# Power_Supply_No_Slo_Start.net
KiCad netlist of a schematic drawn in EAGLE
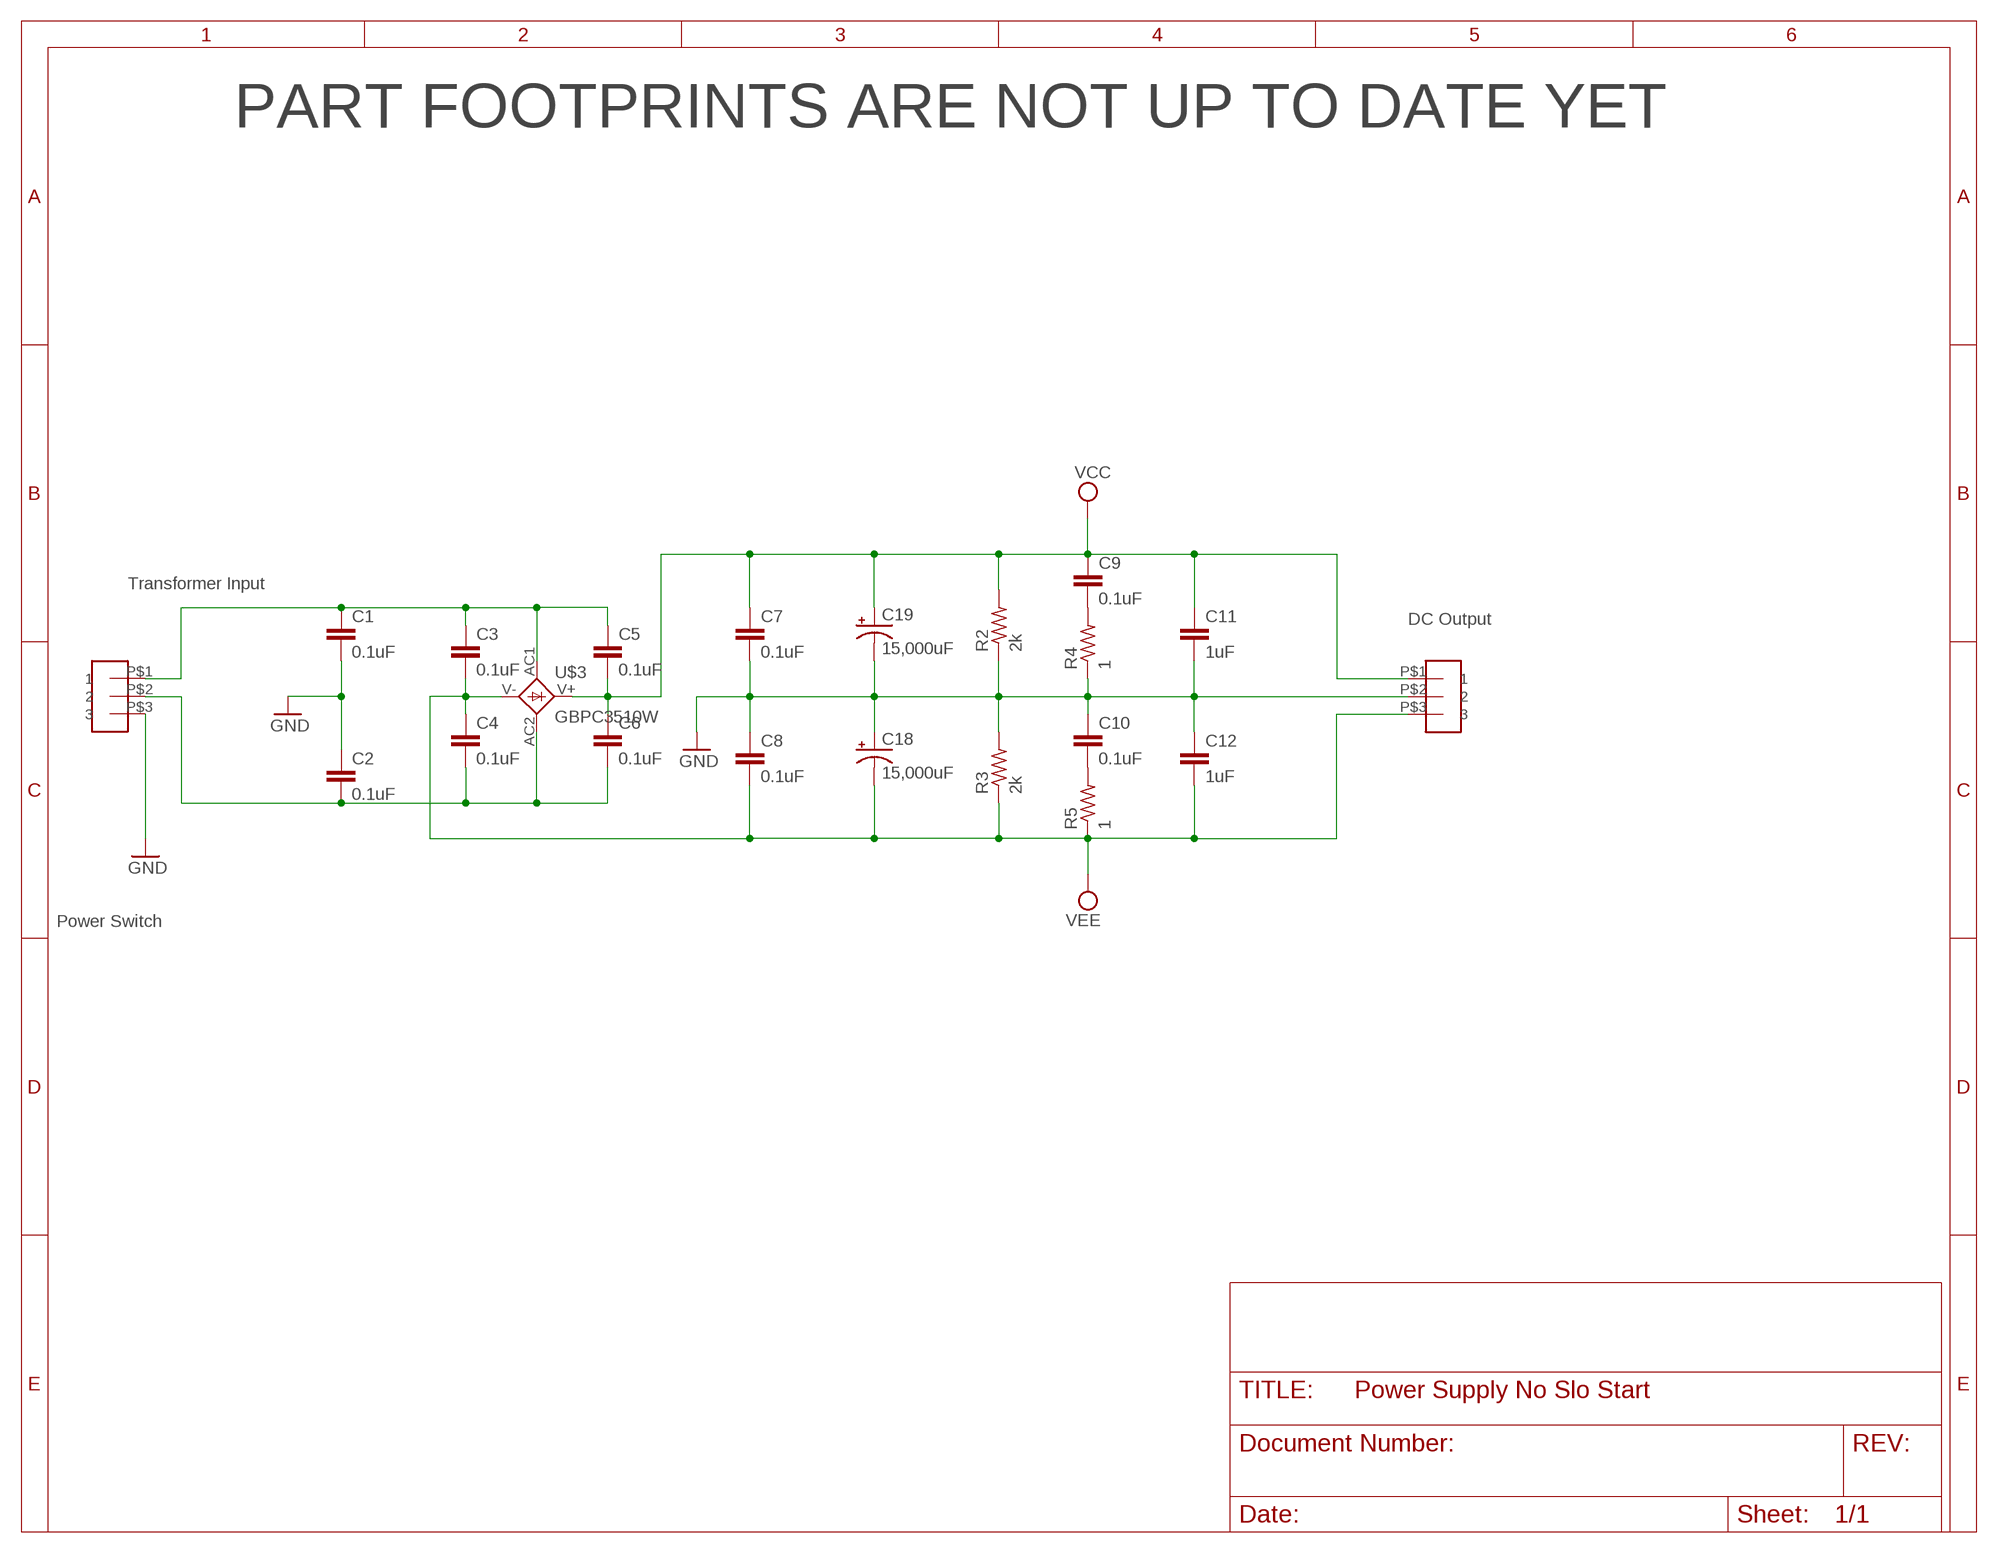
[diagram p0: schematic, sheet 1]

(export (version "E")
  (design (tool "Eeschema 10.0.6"))
  (components
    (comp (ref "C1")
      (value "0.1uF")
      (footprint "eagle-import:C102-064X133")
      (libsource (lib "eagle-import") (part "C-EU102-064X133"))
    )
    (comp (ref "C2")
      (value "0.1uF")
      (footprint "eagle-import:C102-064X133")
      (libsource (lib "eagle-import") (part "C-EU102-064X133"))
    )
    (comp (ref "C3")
      (value "0.1uF")
      (footprint "eagle-import:C075-052X106")
      (libsource (lib "eagle-import") (part "C-EU075-052X106"))
    )
    (comp (ref "C4")
      (value "0.1uF")
      (footprint "eagle-import:C075-052X106")
      (libsource (lib "eagle-import") (part "C-EU075-052X106"))
    )
    (comp (ref "C5")
      (value "0.1uF")
      (footprint "eagle-import:C075-052X106")
      (libsource (lib "eagle-import") (part "C-EU075-052X106"))
    )
    (comp (ref "C6")
      (value "0.1uF")
      (footprint "eagle-import:C075-052X106")
      (libsource (lib "eagle-import") (part "C-EU075-052X106"))
    )
    (comp (ref "C7")
      (value "0.1uF")
      (footprint "eagle-import:C102-064X133")
      (libsource (lib "eagle-import") (part "C-EU102-064X133"))
    )
    (comp (ref "C8")
      (value "0.1uF")
      (footprint "eagle-import:C102-064X133")
      (libsource (lib "eagle-import") (part "C-EU102-064X133"))
    )
    (comp (ref "C9")
      (value "0.1uF")
      (footprint "eagle-import:C102-064X133")
      (libsource (lib "eagle-import") (part "C-EU102-064X133"))
    )
    (comp (ref "C10")
      (value "0.1uF")
      (footprint "eagle-import:C102-064X133")
      (libsource (lib "eagle-import") (part "C-EU102-064X133"))
    )
    (comp (ref "C11")
      (value "1uF")
      (footprint "eagle-import:C102-064X133")
      (libsource (lib "eagle-import") (part "C-EU102-064X133"))
    )
    (comp (ref "C12")
      (value "1uF")
      (footprint "eagle-import:C102-064X133")
      (libsource (lib "eagle-import") (part "C-EU102-064X133"))
    )
    (comp (ref "C18")
      (value "15,000uF")
      (footprint "eagle-import:PHI-35")
      (libsource (lib "eagle-import") (part "LNR1K153MSE"))
    )
    (comp (ref "C19")
      (value "15,000uF")
      (footprint "eagle-import:PHI-35")
      (libsource (lib "eagle-import") (part "LNR1K153MSE"))
    )
    (comp (ref "R2")
      (value "2k")
      (footprint "eagle-import:VTA52")
      (libsource (lib "eagle-import") (part "R-US_VTA52"))
    )
    (comp (ref "R3")
      (value "2k")
      (footprint "eagle-import:VTA52")
      (libsource (lib "eagle-import") (part "R-US_VTA52"))
    )
    (comp (ref "R4")
      (value "1")
      (footprint "eagle-import:0411_12")
      (libsource (lib "eagle-import") (part "R-US_0411/12"))
    )
    (comp (ref "R5")
      (value "1")
      (footprint "eagle-import:0411_12")
      (libsource (lib "eagle-import") (part "R-US_0411/12"))
    )
    (comp (ref "U$1")
      (value "3PIN_3.25MM")
      (footprint "eagle-import:3PIN_SCREW_EYELET")
      (libsource (lib "eagle-import") (part "3PIN_3.25MM"))
    )
    (comp (ref "U$2")
      (value "3PIN_3.25MM")
      (footprint "eagle-import:3PIN_SCREW_EYELET")
      (libsource (lib "eagle-import") (part "3PIN_3.25MM"))
    )
    (comp (ref "U$3")
      (value "GBPC3510W")
      (footprint "eagle-import:GBPC3510W")
      (libsource (lib "eagle-import") (part "GBPC3510W"))
    )
  )
  (nets
    (net (code "1") (name "GND") (class "Default")
      (node (ref "C1") (pin "2") (pinfunction "2_2") (pintype "passive"))
      (node (ref "C10") (pin "1") (pinfunction "1_1") (pintype "passive"))
      (node (ref "C11") (pin "2") (pinfunction "2_2") (pintype "passive"))
      (node (ref "C12") (pin "1") (pinfunction "1_1") (pintype "passive"))
      (node (ref "C18") (pin "+") (pinfunction "+_+") (pintype "passive"))
      (node (ref "C19") (pin "-") (pinfunction "-_-") (pintype "passive"))
      (node (ref "C2") (pin "1") (pinfunction "1_1") (pintype "passive"))
      (node (ref "C7") (pin "2") (pinfunction "2_2") (pintype "passive"))
      (node (ref "C8") (pin "1") (pinfunction "1_1") (pintype "passive"))
      (node (ref "R2") (pin "1") (pinfunction "1_1") (pintype "passive"))
      (node (ref "R3") (pin "2") (pinfunction "2_2") (pintype "passive"))
      (node (ref "R4") (pin "1") (pinfunction "1_1") (pintype "passive"))
      (node (ref "U$1") (pin "P$3") (pinfunction "3_P$3") (pintype "bidirectional"))
      (node (ref "U$2") (pin "P$2") (pinfunction "2_P$2") (pintype "bidirectional"))
    )
    (net (code "2") (name "Net-(C9-Pad2)") (class "Default")
      (node (ref "C9") (pin "2") (pinfunction "2_2") (pintype "passive"))
      (node (ref "R4") (pin "2") (pinfunction "2_2") (pintype "passive"))
    )
    (net (code "3") (name "Net-(C10-Pad2)") (class "Default")
      (node (ref "C10") (pin "2") (pinfunction "2_2") (pintype "passive"))
      (node (ref "R5") (pin "2") (pinfunction "2_2") (pintype "passive"))
    )
    (net (code "4") (name "Net-(U$1-1)") (class "Default")
      (node (ref "C1") (pin "1") (pinfunction "1_1") (pintype "passive"))
      (node (ref "C3") (pin "1") (pinfunction "1_1") (pintype "passive"))
      (node (ref "C5") (pin "1") (pinfunction "1_1") (pintype "passive"))
      (node (ref "U$1") (pin "P$1") (pinfunction "1_P$1") (pintype "bidirectional"))
      (node (ref "U$3") (pin "AC1") (pinfunction "AC1_AC1") (pintype "passive"))
    )
    (net (code "5") (name "Net-(U$1-2)") (class "Default")
      (node (ref "C2") (pin "2") (pinfunction "2_2") (pintype "passive"))
      (node (ref "C4") (pin "2") (pinfunction "2_2") (pintype "passive"))
      (node (ref "C6") (pin "2") (pinfunction "2_2") (pintype "passive"))
      (node (ref "U$1") (pin "P$2") (pinfunction "2_P$2") (pintype "bidirectional"))
      (node (ref "U$3") (pin "AC2") (pinfunction "AC2_AC2") (pintype "passive"))
    )
    (net (code "6") (name "VCC") (class "Default")
      (node (ref "C11") (pin "1") (pinfunction "1_1") (pintype "passive"))
      (node (ref "C19") (pin "+") (pinfunction "+_+") (pintype "passive"))
      (node (ref "C5") (pin "2") (pinfunction "2_2") (pintype "passive"))
      (node (ref "C6") (pin "1") (pinfunction "1_1") (pintype "passive"))
      (node (ref "C7") (pin "1") (pinfunction "1_1") (pintype "passive"))
      (node (ref "C9") (pin "1") (pinfunction "1_1") (pintype "passive"))
      (node (ref "R2") (pin "2") (pinfunction "2_2") (pintype "passive"))
      (node (ref "U$2") (pin "P$1") (pinfunction "1_P$1") (pintype "bidirectional"))
      (node (ref "U$3") (pin "V+") (pinfunction "+_V+") (pintype "passive"))
    )
    (net (code "7") (name "VEE") (class "Default")
      (node (ref "C12") (pin "2") (pinfunction "2_2") (pintype "passive"))
      (node (ref "C18") (pin "-") (pinfunction "-_-") (pintype "passive"))
      (node (ref "C3") (pin "2") (pinfunction "2_2") (pintype "passive"))
      (node (ref "C4") (pin "1") (pinfunction "1_1") (pintype "passive"))
      (node (ref "C8") (pin "2") (pinfunction "2_2") (pintype "passive"))
      (node (ref "R3") (pin "1") (pinfunction "1_1") (pintype "passive"))
      (node (ref "R5") (pin "1") (pinfunction "1_1") (pintype "passive"))
      (node (ref "U$2") (pin "P$3") (pinfunction "3_P$3") (pintype "bidirectional"))
      (node (ref "U$3") (pin "V-") (pinfunction "-_V-") (pintype "passive"))
    )
  )
)
